# BT_RN42_schematic.net
KiCad netlist of a schematic drawn in EAGLE
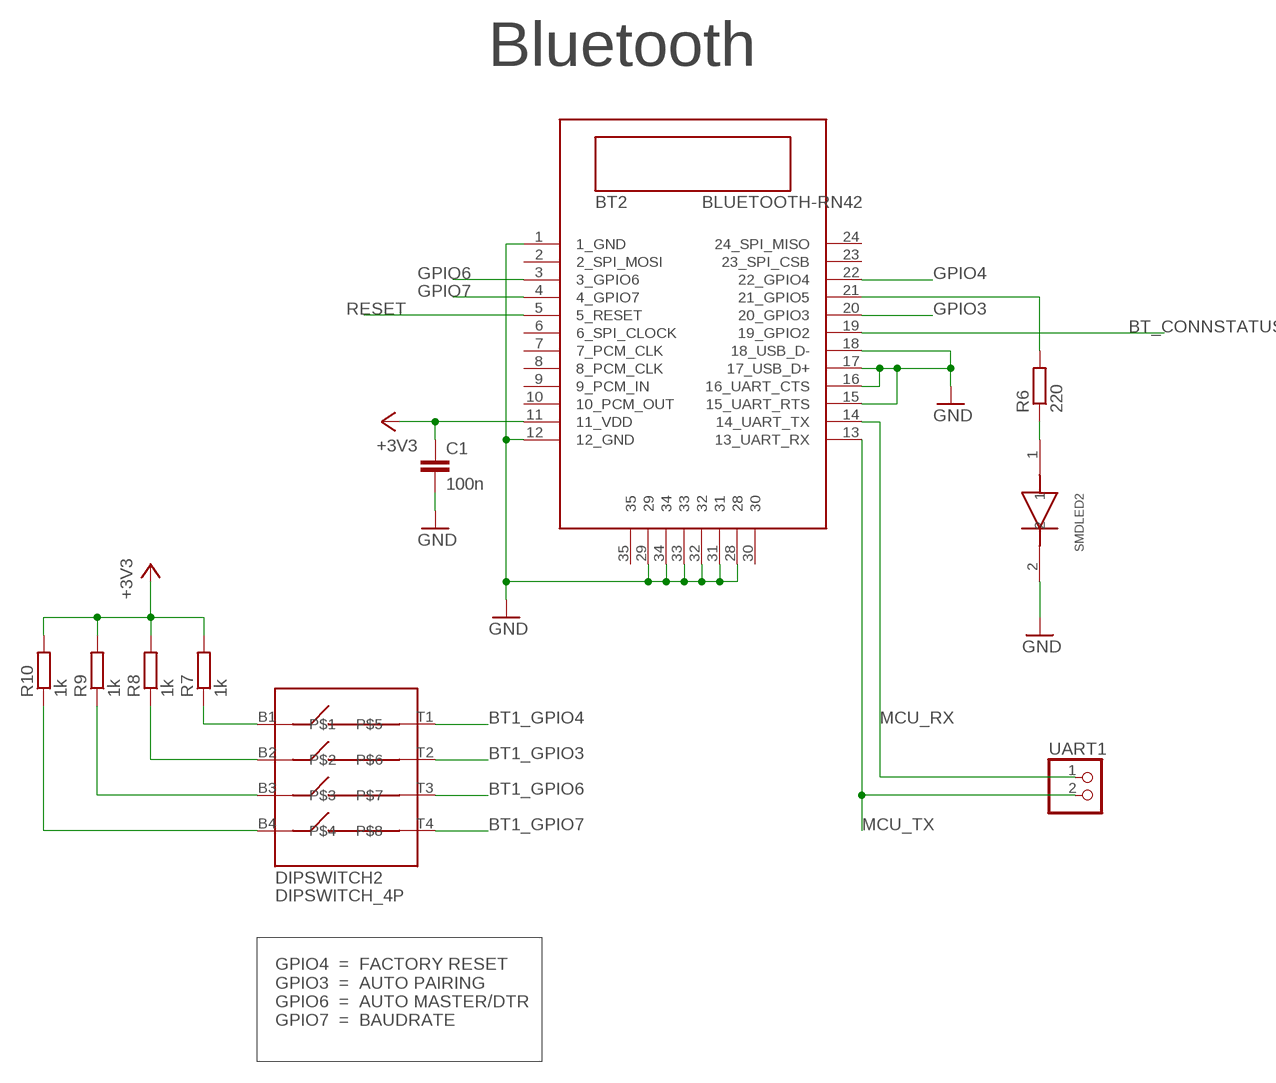
[diagram p0: schematic, sheet 1]

(export (version "E")
  (design (tool "Eeschema 10.0.6"))
  (components
    (comp (ref "BT2")
      (value "BLUETOOTH-RN42")
      (footprint "eagle-import:RN42")
      (libsource (lib "eagle-import") (part "BLUETOOTH-RN42"))
    )
    (comp (ref "C1")
      (value "100n")
      (footprint "eagle-import:C0805")
      (libsource (lib "eagle-import") (part "C-EUC0805"))
    )
    (comp (ref "DIPSWITCH2")
      (value "DIPSWITCH_4P")
      (footprint "eagle-import:DIPSWITCH4P")
      (libsource (lib "eagle-import") (part "DIPSWITCH_4P"))
    )
    (comp (ref "R6")
      (value "220")
      (footprint "eagle-import:R0805")
      (libsource (lib "eagle-import") (part "R-EU_R0805"))
    )
    (comp (ref "R7")
      (value "1k")
      (footprint "eagle-import:R0805")
      (libsource (lib "eagle-import") (part "R-EU_R0805"))
    )
    (comp (ref "R8")
      (value "1k")
      (footprint "eagle-import:R0805")
      (libsource (lib "eagle-import") (part "R-EU_R0805"))
    )
    (comp (ref "R9")
      (value "1k")
      (footprint "eagle-import:R0805")
      (libsource (lib "eagle-import") (part "R-EU_R0805"))
    )
    (comp (ref "R10")
      (value "1k")
      (footprint "eagle-import:R0805")
      (libsource (lib "eagle-import") (part "R-EU_R0805"))
    )
    (comp (ref "SMDLED2")
      (value "SMD_LED")
      (footprint "eagle-import:SMD_LED_CUSTOM")
      (libsource (lib "eagle-import") (part "SMD_LED"))
    )
    (comp (ref "UART1")
      (value "PINHD-1X2")
      (footprint "eagle-import:1X02")
      (libsource (lib "eagle-import") (part "PINHD-1X2"))
    )
  )
  (nets
    (net (code "1") (name "+3V3") (class "Default")
      (node (ref "BT2") (pin "11") (pinfunction "11_VDD_11") (pintype "bidirectional"))
      (node (ref "C1") (pin "1") (pinfunction "1_1") (pintype "passive"))
      (node (ref "R10") (pin "2") (pinfunction "2_2") (pintype "passive"))
      (node (ref "R7") (pin "2") (pinfunction "2_2") (pintype "passive"))
      (node (ref "R8") (pin "2") (pinfunction "2_2") (pintype "passive"))
      (node (ref "R9") (pin "2") (pinfunction "2_2") (pintype "passive"))
    )
    (net (code "2") (name "/BT1_GPIO3") (class "Default")
      (node (ref "DIPSWITCH2") (pin "T2") (pinfunction "P$6_T2") (pintype "bidirectional"))
    )
    (net (code "3") (name "/BT1_GPIO4") (class "Default")
      (node (ref "DIPSWITCH2") (pin "T1") (pinfunction "P$5_T1") (pintype "bidirectional"))
    )
    (net (code "4") (name "/BT1_GPIO6") (class "Default")
      (node (ref "DIPSWITCH2") (pin "T3") (pinfunction "P$7_T3") (pintype "bidirectional"))
    )
    (net (code "5") (name "/BT1_GPIO7") (class "Default")
      (node (ref "DIPSWITCH2") (pin "T4") (pinfunction "P$8_T4") (pintype "bidirectional"))
    )
    (net (code "6") (name "/BT_CONNSTATUS") (class "Default")
      (node (ref "BT2") (pin "19") (pinfunction "19_GPIO2_19") (pintype "bidirectional"))
    )
    (net (code "7") (name "/GPIO3") (class "Default")
      (node (ref "BT2") (pin "20") (pinfunction "20_GPIO3_20") (pintype "bidirectional"))
    )
    (net (code "8") (name "/GPIO4") (class "Default")
      (node (ref "BT2") (pin "22") (pinfunction "22_GPIO4_22") (pintype "bidirectional"))
    )
    (net (code "9") (name "/GPIO6") (class "Default")
      (node (ref "BT2") (pin "3") (pinfunction "3_GPIO6_3") (pintype "bidirectional"))
    )
    (net (code "10") (name "/GPIO7") (class "Default")
      (node (ref "BT2") (pin "4") (pinfunction "4_GPIO7_4") (pintype "bidirectional"))
    )
    (net (code "11") (name "/MCU_RX") (class "Default")
      (node (ref "BT2") (pin "14") (pinfunction "14_UART_TX_14") (pintype "bidirectional"))
      (node (ref "UART1") (pin "1") (pinfunction "1_1") (pintype "passive"))
    )
    (net (code "12") (name "/MCU_TX") (class "Default")
      (node (ref "BT2") (pin "13") (pinfunction "13_UART_RX_13") (pintype "bidirectional"))
      (node (ref "UART1") (pin "2") (pinfunction "2_2") (pintype "passive"))
    )
    (net (code "13") (name "/RESET") (class "Default")
      (node (ref "BT2") (pin "5") (pinfunction "5_RESET_5") (pintype "bidirectional"))
    )
    (net (code "14") (name "GND") (class "Default")
      (node (ref "BT2") (pin "1") (pinfunction "1_GND_1") (pintype "bidirectional"))
      (node (ref "BT2") (pin "12") (pinfunction "12_GND_12") (pintype "bidirectional"))
      (node (ref "BT2") (pin "15") (pinfunction "15_UART_RTS_15") (pintype "bidirectional"))
      (node (ref "BT2") (pin "16") (pinfunction "16_UART_CTS_16") (pintype "bidirectional"))
      (node (ref "BT2") (pin "17") (pinfunction "17_USB_D+_17") (pintype "bidirectional"))
      (node (ref "BT2") (pin "18") (pinfunction "18_USB_D-_18") (pintype "bidirectional"))
      (node (ref "BT2") (pin "28") (pinfunction "28_28") (pintype "bidirectional"))
      (node (ref "BT2") (pin "29") (pinfunction "29_29") (pintype "bidirectional"))
      (node (ref "BT2") (pin "31") (pinfunction "31_31") (pintype "bidirectional"))
      (node (ref "BT2") (pin "32") (pinfunction "32_32") (pintype "bidirectional"))
      (node (ref "BT2") (pin "33") (pinfunction "33_33") (pintype "bidirectional"))
      (node (ref "BT2") (pin "34") (pinfunction "34_34") (pintype "bidirectional"))
      (node (ref "C1") (pin "2") (pinfunction "2_2") (pintype "passive"))
      (node (ref "SMDLED2") (pin "2") (pinfunction "2_2") (pintype "bidirectional"))
    )
    (net (code "15") (name "Net-(BT2-21_GPIO5)") (class "Default")
      (node (ref "BT2") (pin "21") (pinfunction "21_GPIO5_21") (pintype "bidirectional"))
      (node (ref "R6") (pin "2") (pinfunction "2_2") (pintype "passive"))
    )
    (net (code "16") (name "Net-(DIPSWITCH2-P$1)") (class "Default")
      (node (ref "DIPSWITCH2") (pin "B1") (pinfunction "P$1_B1") (pintype "bidirectional"))
      (node (ref "R7") (pin "1") (pinfunction "1_1") (pintype "passive"))
    )
    (net (code "17") (name "Net-(DIPSWITCH2-P$2)") (class "Default")
      (node (ref "DIPSWITCH2") (pin "B2") (pinfunction "P$2_B2") (pintype "bidirectional"))
      (node (ref "R8") (pin "1") (pinfunction "1_1") (pintype "passive"))
    )
    (net (code "18") (name "Net-(DIPSWITCH2-P$3)") (class "Default")
      (node (ref "DIPSWITCH2") (pin "B3") (pinfunction "P$3_B3") (pintype "bidirectional"))
      (node (ref "R9") (pin "1") (pinfunction "1_1") (pintype "passive"))
    )
    (net (code "19") (name "Net-(DIPSWITCH2-P$4)") (class "Default")
      (node (ref "DIPSWITCH2") (pin "B4") (pinfunction "P$4_B4") (pintype "bidirectional"))
      (node (ref "R10") (pin "1") (pinfunction "1_1") (pintype "passive"))
    )
    (net (code "20") (name "Net-(R6-Pad1)") (class "Default")
      (node (ref "R6") (pin "1") (pinfunction "1_1") (pintype "passive"))
      (node (ref "SMDLED2") (pin "1") (pinfunction "1_1") (pintype "bidirectional"))
    )
    (net (code "21") (name "unconnected-(BT2-2_SPI_MOSI-Pad2)") (class "Default")
      (node (ref "BT2") (pin "2") (pinfunction "2_SPI_MOSI_2") (pintype "bidirectional"))
    )
    (net (code "22") (name "unconnected-(BT2-6_SPI_CLOCK-Pad6)") (class "Default")
      (node (ref "BT2") (pin "6") (pinfunction "6_SPI_CLOCK_6") (pintype "bidirectional"))
    )
    (net (code "23") (name "unconnected-(BT2-7_PCM_CLK-Pad7)") (class "Default")
      (node (ref "BT2") (pin "7") (pinfunction "7_PCM_CLK_7") (pintype "bidirectional"))
    )
    (net (code "24") (name "unconnected-(BT2-8_PCM_CLK-Pad8)") (class "Default")
      (node (ref "BT2") (pin "8") (pinfunction "8_PCM_CLK_8") (pintype "bidirectional"))
    )
    (net (code "25") (name "unconnected-(BT2-9_PCM_IN-Pad9)") (class "Default")
      (node (ref "BT2") (pin "9") (pinfunction "9_PCM_IN_9") (pintype "bidirectional"))
    )
    (net (code "26") (name "unconnected-(BT2-10_PCM_OUT-Pad10)") (class "Default")
      (node (ref "BT2") (pin "10") (pinfunction "10_PCM_OUT_10") (pintype "bidirectional"))
    )
    (net (code "27") (name "unconnected-(BT2-23_SPI_CSB-Pad23)") (class "Default")
      (node (ref "BT2") (pin "23") (pinfunction "23_SPI_CSB_23") (pintype "bidirectional"))
    )
    (net (code "28") (name "unconnected-(BT2-24_SPI_MISO-Pad24)") (class "Default")
      (node (ref "BT2") (pin "24") (pinfunction "24_SPI_MISO_24") (pintype "bidirectional"))
    )
    (net (code "29") (name "unconnected-(BT2-Pad30)") (class "Default")
      (node (ref "BT2") (pin "30") (pinfunction "30_30") (pintype "bidirectional"))
    )
    (net (code "30") (name "unconnected-(BT2-Pad35)") (class "Default")
      (node (ref "BT2") (pin "35") (pinfunction "35_35") (pintype "bidirectional"))
    )
  )
)
